# step_down_module.net
KiCad netlist of a schematic drawn in EAGLE
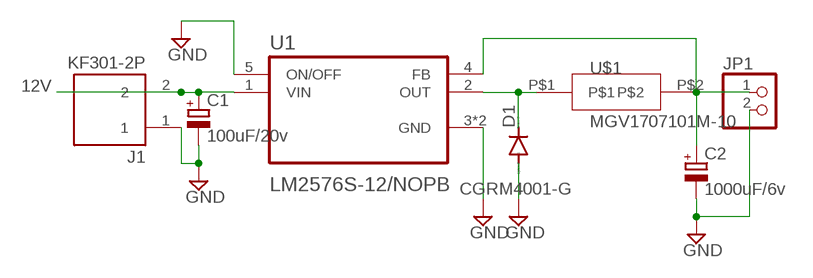
[diagram p0: schematic, sheet 1]

(export (version "E")
  (design (tool "Eeschema 10.0.6"))
  (components
    (comp (ref "C1")
      (value "100uF/20v")
      (footprint "eagle-import:D_7343-31W")
      (libsource (lib "eagle-import") (part "CPOL-EUD/7343-31W"))
    )
    (comp (ref "C2")
      (value "1000uF/6v")
      (footprint "eagle-import:D_7343-31W")
      (libsource (lib "eagle-import") (part "CPOL-EUD/7343-31W"))
    )
    (comp (ref "D1")
      (value "CGRM4001-G")
      (footprint "eagle-import:SOD-123_MINI-SMA")
      (libsource (lib "eagle-import") (part "CGRM400-G1"))
    )
    (comp (ref "J1")
      (value "KF301-2P")
      (footprint "eagle-import:HANDSON_KF301-2P")
      (fields (field (name "MF") "Handson Technology"))
      (libsource (lib "eagle-import") (part "KF301-2P"))
    )
    (comp (ref "JP1")
      (value "PINHD-1X2")
      (footprint "eagle-import:1X02")
      (libsource (lib "eagle-import") (part "PINHD-1X2"))
    )
    (comp (ref "U$1")
      (value "MGV1707101M-10")
      (footprint "eagle-import:MGV1707101M-10")
      (libsource (lib "eagle-import") (part "MGV1707101M-10"))
    )
    (comp (ref "U1")
      (value "LM2576S-12/NOPB")
      (footprint "eagle-import:VREG_TPS79625KTTR")
      (fields (field (name "MF") "Texas Instruments"))
      (libsource (lib "eagle-import") (part "LM2576S-12/NOPB"))
    )
  )
  (nets
    (net (code "1") (name "/12V") (class "Default")
      (node (ref "C1") (pin "+") (pinfunction "+_+") (pintype "passive"))
      (node (ref "J1") (pin "2") (pinfunction "2_2") (pintype "passive"))
      (node (ref "U1") (pin "1") (pinfunction "VIN_1") (pintype "input"))
    )
    (net (code "2") (name "GND") (class "Default")
      (node (ref "C1") (pin "-") (pinfunction "-_-") (pintype "passive"))
      (node (ref "C2") (pin "-") (pinfunction "-_-") (pintype "passive"))
      (node (ref "D1") (pin "A") (pinfunction "A_A") (pintype "passive"))
      (node (ref "J1") (pin "1") (pinfunction "1_1") (pintype "passive"))
      (node (ref "JP1") (pin "2") (pinfunction "2_2") (pintype "passive"))
      (node (ref "U1") (pin "3") (pinfunction "GND_3") (pintype "power_in"))
      (node (ref "U1") (pin "5") (pinfunction "ON/OFF_5") (pintype "input"))
      (node (ref "U1") (pin "6") (pinfunction "GND_6") (pintype "power_in"))
    )
    (net (code "3") (name "Net-(U1-FB)") (class "Default")
      (node (ref "C2") (pin "+") (pinfunction "+_+") (pintype "passive"))
      (node (ref "JP1") (pin "1") (pinfunction "1_1") (pintype "passive"))
      (node (ref "U$1") (pin "P$2") (pinfunction "P$2_P$2") (pintype "bidirectional"))
      (node (ref "U1") (pin "4") (pinfunction "FB_4") (pintype "output"))
    )
    (net (code "4") (name "Net-(U1-OUT)") (class "Default")
      (node (ref "D1") (pin "C") (pinfunction "C_C") (pintype "passive"))
      (node (ref "U$1") (pin "P$1") (pinfunction "P$1_P$1") (pintype "bidirectional"))
      (node (ref "U1") (pin "2") (pinfunction "OUT_2") (pintype "output"))
    )
  )
)
